# Digital_Input.net
KiCad netlist of a schematic drawn in Altium Designer
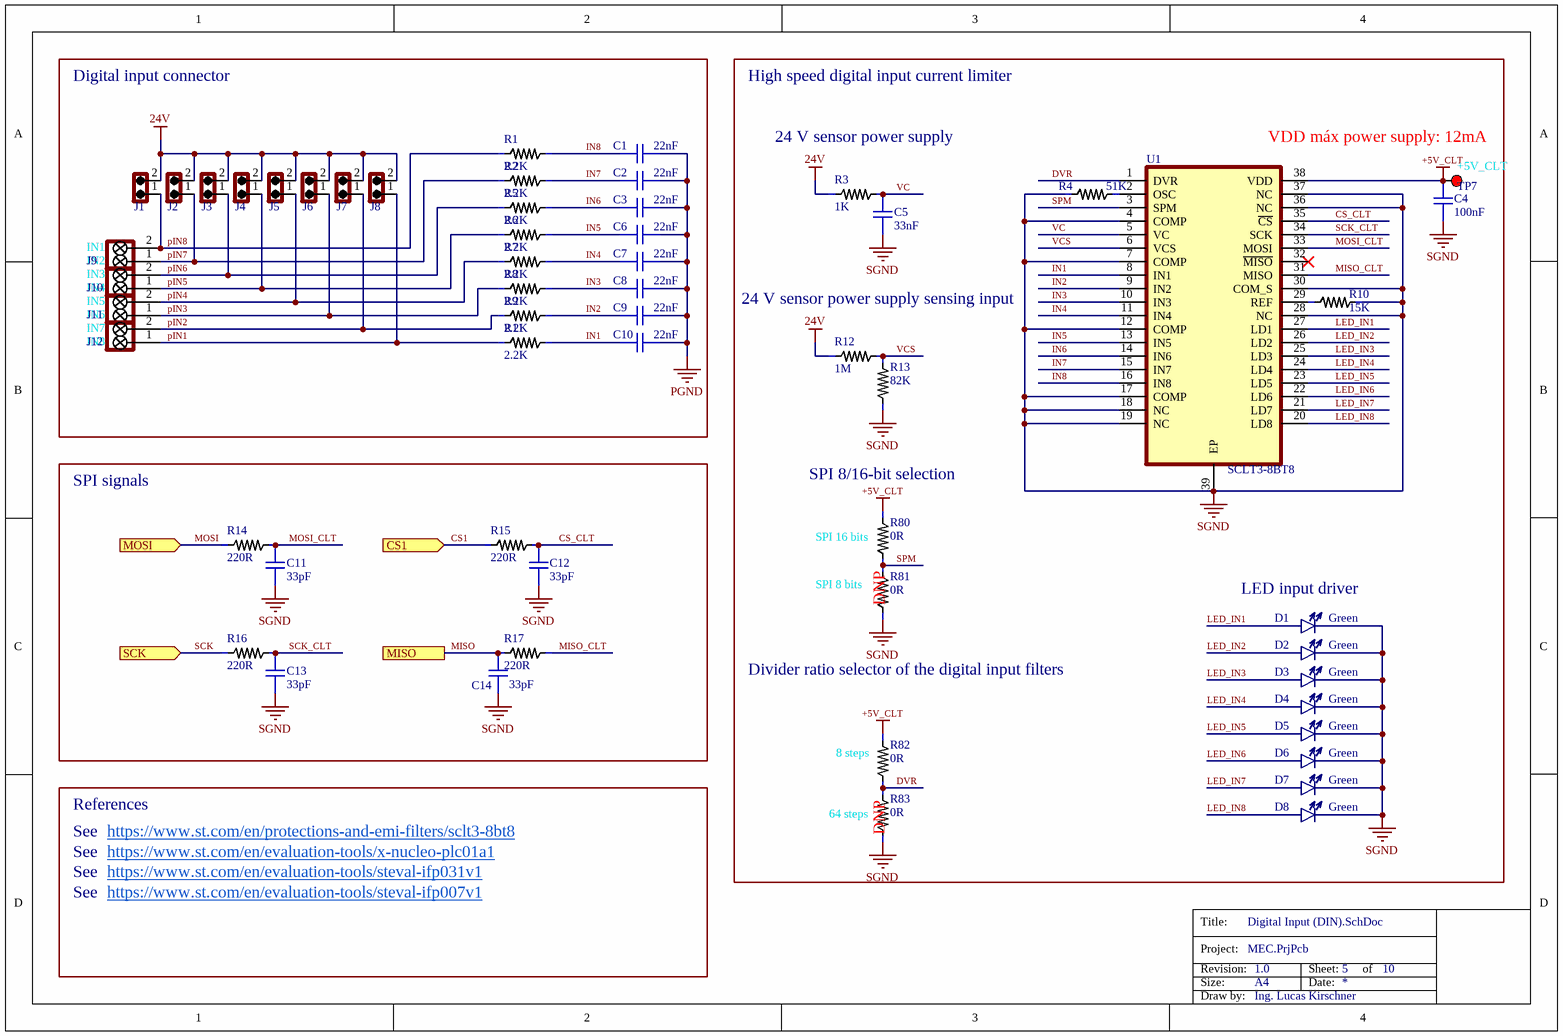
[diagram p0: Digital Input (DIN).SchDoc]

(export (version "E")
  (design (tool "Eeschema 10.0.6"))
  (components
    (comp (ref "C1")
      (value "22nF")
      (footprint "CAPC2012N")
      (description "Multilayer Ceramic Capacitors MLCC - SMD/SMT 100 V 0.022 uF X7R 0805 10%")
      (fields (field (name "PART NUMBER") "CC0805KRX7R0BB223") (field (name "MANUFACTURER") "YAGEO"))
      (libsource (lib "SchLib") (part "C-MLCC-22nF-100V-10%-0805"))
    )
    (comp (ref "C2")
      (value "22nF")
      (footprint "CAPC2012N")
      (description "Multilayer Ceramic Capacitors MLCC - SMD/SMT 100 V 0.022 uF X7R 0805 10%")
      (fields (field (name "PART NUMBER") "CC0805KRX7R0BB223") (field (name "MANUFACTURER") "YAGEO"))
      (libsource (lib "SchLib") (part "C-MLCC-22nF-100V-10%-0805"))
    )
    (comp (ref "C3")
      (value "22nF")
      (footprint "CAPC2012N")
      (description "Multilayer Ceramic Capacitors MLCC - SMD/SMT 100 V 0.022 uF X7R 0805 10%")
      (fields (field (name "PART NUMBER") "CC0805KRX7R0BB223") (field (name "MANUFACTURER") "YAGEO"))
      (libsource (lib "SchLib") (part "C-MLCC-22nF-100V-10%-0805"))
    )
    (comp (ref "C4")
      (value "100nF")
      (footprint "CAPC1005N")
      (description "Multilayer Ceramic Capacitors MLCC - SMD/SMT 50 V 0.1uF X7R 0402 10%")
      (fields (field (name "PART NUMBER") "CC0402KRX5R9BB104") (field (name "MANUFACTURER") "YAGEO"))
      (libsource (lib "SchLib") (part "C-MLCC-100nF-50V-10%-0402"))
    )
    (comp (ref "C5")
      (value "33nF")
      (footprint "CAPC2012N")
      (description "Multilayer Ceramic Capacitors MLCC - SMD/SMT 100 V 0.033 uF X7R 0805 10%")
      (fields (field (name "PART NUMBER") "CC0805KKX7R0BB333") (field (name "MANUFACTURER") "YAGEO"))
      (libsource (lib "SchLib") (part "C-MLCC-33nF-100V-10%-0805"))
    )
    (comp (ref "C6")
      (value "22nF")
      (footprint "CAPC2012N")
      (description "Multilayer Ceramic Capacitors MLCC - SMD/SMT 100 V 0.022 uF X7R 0805 10%")
      (fields (field (name "PART NUMBER") "CC0805KRX7R0BB223") (field (name "MANUFACTURER") "YAGEO"))
      (libsource (lib "SchLib") (part "C-MLCC-22nF-100V-10%-0805"))
    )
    (comp (ref "C7")
      (value "22nF")
      (footprint "CAPC2012N")
      (description "Multilayer Ceramic Capacitors MLCC - SMD/SMT 100 V 0.022 uF X7R 0805 10%")
      (fields (field (name "PART NUMBER") "CC0805KRX7R0BB223") (field (name "MANUFACTURER") "YAGEO"))
      (libsource (lib "SchLib") (part "C-MLCC-22nF-100V-10%-0805"))
    )
    (comp (ref "C8")
      (value "22nF")
      (footprint "CAPC2012N")
      (description "Multilayer Ceramic Capacitors MLCC - SMD/SMT 100 V 0.022 uF X7R 0805 10%")
      (fields (field (name "PART NUMBER") "CC0805KRX7R0BB223") (field (name "MANUFACTURER") "YAGEO"))
      (libsource (lib "SchLib") (part "C-MLCC-22nF-100V-10%-0805"))
    )
    (comp (ref "C9")
      (value "22nF")
      (footprint "CAPC2012N")
      (description "Multilayer Ceramic Capacitors MLCC - SMD/SMT 100 V 0.022 uF X7R 0805 10%")
      (fields (field (name "PART NUMBER") "CC0805KRX7R0BB223") (field (name "MANUFACTURER") "YAGEO"))
      (libsource (lib "SchLib") (part "C-MLCC-22nF-100V-10%-0805"))
    )
    (comp (ref "C10")
      (value "22nF")
      (footprint "CAPC2012N")
      (description "Multilayer Ceramic Capacitors MLCC - SMD/SMT 100 V 0.022 uF X7R 0805 10%")
      (fields (field (name "PART NUMBER") "CC0805KRX7R0BB223") (field (name "MANUFACTURER") "YAGEO"))
      (libsource (lib "SchLib") (part "C-MLCC-22nF-100V-10%-0805"))
    )
    (comp (ref "C11")
      (value "33pF")
      (footprint "CAPC1005N")
      (description "Multilayer Ceramic Capacitors MLCC - SMD/SMT 50 V 33 pF C0G 0402 1%")
      (fields (field (name "PART NUMBER") "CC0402KRNPO9BN330") (field (name "MANUFACTURER") "YAGEO"))
      (libsource (lib "SchLib") (part "C-MLCC-33pF-50V-10%-0402"))
    )
    (comp (ref "C12")
      (value "33pF")
      (footprint "CAPC1005N")
      (description "Multilayer Ceramic Capacitors MLCC - SMD/SMT 50 V 33 pF C0G 0402 1%")
      (fields (field (name "PART NUMBER") "CC0402KRNPO9BN330") (field (name "MANUFACTURER") "YAGEO"))
      (libsource (lib "SchLib") (part "C-MLCC-33pF-50V-10%-0402"))
    )
    (comp (ref "C13")
      (value "33pF")
      (footprint "CAPC1005N")
      (description "Multilayer Ceramic Capacitors MLCC - SMD/SMT 50 V 33 pF C0G 0402 1%")
      (fields (field (name "PART NUMBER") "CC0402KRNPO9BN330") (field (name "MANUFACTURER") "YAGEO"))
      (libsource (lib "SchLib") (part "C-MLCC-33pF-50V-10%-0402"))
    )
    (comp (ref "C14")
      (value "33pF")
      (footprint "CAPC1005N")
      (description "Multilayer Ceramic Capacitors MLCC - SMD/SMT 50 V 33 pF C0G 0402 1%")
      (fields (field (name "PART NUMBER") "CC0402KRNPO9BN330") (field (name "MANUFACTURER") "YAGEO"))
      (libsource (lib "SchLib") (part "C-MLCC-33pF-50V-10%-0402"))
    )
    (comp (ref "D1")
      (value "Green")
      (footprint "LEDC1608X80N_GREEN")
      (description "Standard Single Color LEDs 0603 Green")
      (fields (field (name "PART NUMBER") "LTST-C190KGKT") (field (name "MANUFACTURER") "LITEON"))
      (libsource (lib "SchLib") (part "D-LED-GREEN-2V-20mA-0603"))
    )
    (comp (ref "D2")
      (value "Green")
      (footprint "LEDC1608X80N_GREEN")
      (description "Standard Single Color LEDs 0603 Green")
      (fields (field (name "PART NUMBER") "LTST-C190KGKT") (field (name "MANUFACTURER") "LITEON"))
      (libsource (lib "SchLib") (part "D-LED-GREEN-2V-20mA-0603"))
    )
    (comp (ref "D3")
      (value "Green")
      (footprint "LEDC1608X80N_GREEN")
      (description "Standard Single Color LEDs 0603 Green")
      (fields (field (name "PART NUMBER") "LTST-C190KGKT") (field (name "MANUFACTURER") "LITEON"))
      (libsource (lib "SchLib") (part "D-LED-GREEN-2V-20mA-0603"))
    )
    (comp (ref "D4")
      (value "Green")
      (footprint "LEDC1608X80N_GREEN")
      (description "Standard Single Color LEDs 0603 Green")
      (fields (field (name "PART NUMBER") "LTST-C190KGKT") (field (name "MANUFACTURER") "LITEON"))
      (libsource (lib "SchLib") (part "D-LED-GREEN-2V-20mA-0603"))
    )
    (comp (ref "D5")
      (value "Green")
      (footprint "LEDC1608X80N_GREEN")
      (description "Standard Single Color LEDs 0603 Green")
      (fields (field (name "PART NUMBER") "LTST-C190KGKT") (field (name "MANUFACTURER") "LITEON"))
      (libsource (lib "SchLib") (part "D-LED-GREEN-2V-20mA-0603"))
    )
    (comp (ref "D6")
      (value "Green")
      (footprint "LEDC1608X80N_GREEN")
      (description "Standard Single Color LEDs 0603 Green")
      (fields (field (name "PART NUMBER") "LTST-C190KGKT") (field (name "MANUFACTURER") "LITEON"))
      (libsource (lib "SchLib") (part "D-LED-GREEN-2V-20mA-0603"))
    )
    (comp (ref "D7")
      (value "Green")
      (footprint "LEDC1608X80N_GREEN")
      (description "Standard Single Color LEDs 0603 Green")
      (fields (field (name "PART NUMBER") "LTST-C190KGKT") (field (name "MANUFACTURER") "LITEON"))
      (libsource (lib "SchLib") (part "D-LED-GREEN-2V-20mA-0603"))
    )
    (comp (ref "D8")
      (value "Green")
      (footprint "LEDC1608X80N_GREEN")
      (description "Standard Single Color LEDs 0603 Green")
      (fields (field (name "PART NUMBER") "LTST-C190KGKT") (field (name "MANUFACTURER") "LITEON"))
      (libsource (lib "SchLib") (part "D-LED-GREEN-2V-20mA-0603"))
    )
    (comp (ref "J1")
      (value "Male straight header")
      (footprint "CONH_ML254P-2N")
      (description "Male straight header, 1 row, 2 positions, 2.54mm pitch, through-hole")
      (fields (field (name "PART NUMBER") "10129378-902001BLF") (field (name "MANUFACTURER") "Amphenol FCI"))
      (libsource (lib "SchLib") (part "J-02-2P54-HDR-M-VERT-TH"))
    )
    (comp (ref "J2")
      (value "Male straight header")
      (footprint "CONH_ML254P-2N")
      (description "Male straight header, 1 row, 2 positions, 2.54mm pitch, through-hole")
      (fields (field (name "PART NUMBER") "10129378-902001BLF") (field (name "MANUFACTURER") "Amphenol FCI"))
      (libsource (lib "SchLib") (part "J-02-2P54-HDR-M-VERT-TH"))
    )
    (comp (ref "J3")
      (value "Male straight header")
      (footprint "CONH_ML254P-2N")
      (description "Male straight header, 1 row, 2 positions, 2.54mm pitch, through-hole")
      (fields (field (name "PART NUMBER") "10129378-902001BLF") (field (name "MANUFACTURER") "Amphenol FCI"))
      (libsource (lib "SchLib") (part "J-02-2P54-HDR-M-VERT-TH"))
    )
    (comp (ref "J4")
      (value "Male straight header")
      (footprint "CONH_ML254P-2N")
      (description "Male straight header, 1 row, 2 positions, 2.54mm pitch, through-hole")
      (fields (field (name "PART NUMBER") "10129378-902001BLF") (field (name "MANUFACTURER") "Amphenol FCI"))
      (libsource (lib "SchLib") (part "J-02-2P54-HDR-M-VERT-TH"))
    )
    (comp (ref "J5")
      (value "Male straight header")
      (footprint "CONH_ML254P-2N")
      (description "Male straight header, 1 row, 2 positions, 2.54mm pitch, through-hole")
      (fields (field (name "PART NUMBER") "10129378-902001BLF") (field (name "MANUFACTURER") "Amphenol FCI"))
      (libsource (lib "SchLib") (part "J-02-2P54-HDR-M-VERT-TH"))
    )
    (comp (ref "J6")
      (value "Male straight header")
      (footprint "CONH_ML254P-2N")
      (description "Male straight header, 1 row, 2 positions, 2.54mm pitch, through-hole")
      (fields (field (name "PART NUMBER") "10129378-902001BLF") (field (name "MANUFACTURER") "Amphenol FCI"))
      (libsource (lib "SchLib") (part "J-02-2P54-HDR-M-VERT-TH"))
    )
    (comp (ref "J7")
      (value "Male straight header")
      (footprint "CONH_ML254P-2N")
      (description "Male straight header, 1 row, 2 positions, 2.54mm pitch, through-hole")
      (fields (field (name "PART NUMBER") "10129378-902001BLF") (field (name "MANUFACTURER") "Amphenol FCI"))
      (libsource (lib "SchLib") (part "J-02-2P54-HDR-M-VERT-TH"))
    )
    (comp (ref "J8")
      (value "Male straight header")
      (footprint "CONH_ML254P-2N")
      (description "Male straight header, 1 row, 2 positions, 2.54mm pitch, through-hole")
      (fields (field (name "PART NUMBER") "10129378-902001BLF") (field (name "MANUFACTURER") "Amphenol FCI"))
      (libsource (lib "SchLib") (part "J-02-2P54-HDR-M-VERT-TH"))
    )
    (comp (ref "J9")
      (value "Terminal Blocks")
      (footprint "CONB_FIX508P-2N")
      (description "Pluggable Terminal Blocks 2 Pos 5.08mm pitch Through Hole Header")
      (fields (field (name "MOUSER PART #") "737-EBA-02-D-BU-01") (field (name "MANUFACTURER") "Adam Tech"))
      (libsource (lib "SchLib") (part "J-02-5P08-TERM-F-VERT-TH"))
    )
    (comp (ref "J10")
      (value "Terminal Blocks")
      (footprint "CONB_FIX508P-2N")
      (description "Pluggable Terminal Blocks 2 Pos 5.08mm pitch Through Hole Header")
      (fields (field (name "MOUSER PART #") "737-EBA-02-D-BU-01") (field (name "MANUFACTURER") "Adam Tech"))
      (libsource (lib "SchLib") (part "J-02-5P08-TERM-F-VERT-TH"))
    )
    (comp (ref "J11")
      (value "Terminal Blocks")
      (footprint "CONB_FIX508P-2N")
      (description "Pluggable Terminal Blocks 2 Pos 5.08mm pitch Through Hole Header")
      (fields (field (name "MOUSER PART #") "737-EBA-02-D-BU-01") (field (name "MANUFACTURER") "Adam Tech"))
      (libsource (lib "SchLib") (part "J-02-5P08-TERM-F-VERT-TH"))
    )
    (comp (ref "J12")
      (value "Terminal Blocks")
      (footprint "CONB_FIX508P-2N")
      (description "Pluggable Terminal Blocks 2 Pos 5.08mm pitch Through Hole Header")
      (fields (field (name "MOUSER PART #") "737-EBA-02-D-BU-01") (field (name "MANUFACTURER") "Adam Tech"))
      (libsource (lib "SchLib") (part "J-02-5P08-TERM-F-VERT-TH"))
    )
    (comp (ref "R1")
      (value "2.2K")
      (footprint "RESC2012N")
      (description "Thick Film Resistors - SMD General Purpose Chip Resistor 0805, 2.2kOhms, 1%, 1/8W")
      (fields (field (name "PART NUMBER") "RC0805FR-072K2L") (field (name "MANUFACTURER") "YAGEO"))
      (libsource (lib "SchLib") (part "R-THICK-2K2-125mW-1%-0805"))
    )
    (comp (ref "R2")
      (value "2.2K")
      (footprint "RESC2012N")
      (description "Thick Film Resistors - SMD General Purpose Chip Resistor 0805, 2.2kOhms, 1%, 1/8W")
      (fields (field (name "PART NUMBER") "RC0805FR-072K2L") (field (name "MANUFACTURER") "YAGEO"))
      (libsource (lib "SchLib") (part "R-THICK-2K2-125mW-1%-0805"))
    )
    (comp (ref "R3")
      (value "1K")
      (footprint "RESC2012N")
      (description "Thick Film Resistors - SMD General Purpose Chip Resistor 0805, 1kOhms, 1%, 1/8W")
      (fields (field (name "PART NUMBER") "RC0805FR-071KL") (field (name "MANUFACTURER") "YAGEO"))
      (libsource (lib "SchLib") (part "R-THICK-1K-125mW-1%-0805"))
    )
    (comp (ref "R4")
      (value "51K")
      (footprint "RESC1005N")
      (description "Thick Film Resistors - SMD General Purpose Chip Resistor 0402, 51kOhms, 1%, 1/16W")
      (fields (field (name "PART NUMBER") "RC0402FR-0751KL") (field (name "MANUFACTURER") "YAGEO"))
      (libsource (lib "SchLib") (part "R-THICK-51K-62.5mW-1%-0402"))
    )
    (comp (ref "R5")
      (value "2.2K")
      (footprint "RESC2012N")
      (description "Thick Film Resistors - SMD General Purpose Chip Resistor 0805, 2.2kOhms, 1%, 1/8W")
      (fields (field (name "PART NUMBER") "RC0805FR-072K2L") (field (name "MANUFACTURER") "YAGEO"))
      (libsource (lib "SchLib") (part "R-THICK-2K2-125mW-1%-0805"))
    )
    (comp (ref "R6")
      (value "2.2K")
      (footprint "RESC2012N")
      (description "Thick Film Resistors - SMD General Purpose Chip Resistor 0805, 2.2kOhms, 1%, 1/8W")
      (fields (field (name "PART NUMBER") "RC0805FR-072K2L") (field (name "MANUFACTURER") "YAGEO"))
      (libsource (lib "SchLib") (part "R-THICK-2K2-125mW-1%-0805"))
    )
    (comp (ref "R7")
      (value "2.2K")
      (footprint "RESC2012N")
      (description "Thick Film Resistors - SMD General Purpose Chip Resistor 0805, 2.2kOhms, 1%, 1/8W")
      (fields (field (name "PART NUMBER") "RC0805FR-072K2L") (field (name "MANUFACTURER") "YAGEO"))
      (libsource (lib "SchLib") (part "R-THICK-2K2-125mW-1%-0805"))
    )
    (comp (ref "R8")
      (value "2.2K")
      (footprint "RESC2012N")
      (description "Thick Film Resistors - SMD General Purpose Chip Resistor 0805, 2.2kOhms, 1%, 1/8W")
      (fields (field (name "PART NUMBER") "RC0805FR-072K2L") (field (name "MANUFACTURER") "YAGEO"))
      (libsource (lib "SchLib") (part "R-THICK-2K2-125mW-1%-0805"))
    )
    (comp (ref "R9")
      (value "2.2K")
      (footprint "RESC2012N")
      (description "Thick Film Resistors - SMD General Purpose Chip Resistor 0805, 2.2kOhms, 1%, 1/8W")
      (fields (field (name "PART NUMBER") "RC0805FR-072K2L") (field (name "MANUFACTURER") "YAGEO"))
      (libsource (lib "SchLib") (part "R-THICK-2K2-125mW-1%-0805"))
    )
    (comp (ref "R10")
      (value "15K")
      (footprint "RESC1005N")
      (description "Thick Film Resistors - SMD General Purpose Chip Resistor 0402, 15kOhms, 1%, 1/16W")
      (fields (field (name "PART NUMBER") "RC0402FR-0715KL") (field (name "MANUFACTURER") "YAGEO"))
      (libsource (lib "SchLib") (part "R-THICK-15K-62.5mW-1%-0402"))
    )
    (comp (ref "R11")
      (value "2.2K")
      (footprint "RESC2012N")
      (description "Thick Film Resistors - SMD General Purpose Chip Resistor 0805, 2.2kOhms, 1%, 1/8W")
      (fields (field (name "PART NUMBER") "RC0805FR-072K2L") (field (name "MANUFACTURER") "YAGEO"))
      (libsource (lib "SchLib") (part "R-THICK-2K2-125mW-1%-0805"))
    )
    (comp (ref "R12")
      (value "1M")
      (footprint "RESC2012N")
      (description "Thick Film Resistors - SMD General Purpose Chip Resistor 0805, 1MOhms, 1%, 1/8W")
      (fields (field (name "PART NUMBER") "RC0805FR-071ML") (field (name "MANUFACTURER") "YAGEO"))
      (libsource (lib "SchLib") (part "R-THICK-1M-125mW-1%-0805"))
    )
    (comp (ref "R13")
      (value "82K")
      (footprint "RESC2012N")
      (description "Thick Film Resistors - SMD General Purpose Chip Resistor 0805, 82 kOhms, 1%, 1/8W")
      (fields (field (name "PART NUMBER") "RC0805FR-0782KL") (field (name "MANUFACTURER") "YAGEO"))
      (libsource (lib "SchLib") (part "R-THICK-82K-125mW-1%-0805"))
    )
    (comp (ref "R14")
      (value "220R")
      (footprint "RESC1005N")
      (description "Thick Film Resistors - SMD General Purpose Chip Resistor 0402, 220Ohms, 1%, 1/16W")
      (fields (field (name "PART NUMBER") "RC0402FR-07220RL") (field (name "MANUFACTURER") "YAGEO"))
      (libsource (lib "SchLib") (part "R-THICK-220R-62.5mW-1%-0402"))
    )
    (comp (ref "R15")
      (value "220R")
      (footprint "RESC1005N")
      (description "Thick Film Resistors - SMD General Purpose Chip Resistor 0402, 220Ohms, 1%, 1/16W")
      (fields (field (name "PART NUMBER") "RC0402FR-07220RL") (field (name "MANUFACTURER") "YAGEO"))
      (libsource (lib "SchLib") (part "R-THICK-220R-62.5mW-1%-0402"))
    )
    (comp (ref "R16")
      (value "220R")
      (footprint "RESC1005N")
      (description "Thick Film Resistors - SMD General Purpose Chip Resistor 0402, 220Ohms, 1%, 1/16W")
      (fields (field (name "PART NUMBER") "RC0402FR-07220RL") (field (name "MANUFACTURER") "YAGEO"))
      (libsource (lib "SchLib") (part "R-THICK-220R-62.5mW-1%-0402"))
    )
    (comp (ref "R17")
      (value "220R")
      (footprint "RESC1005N")
      (description "Thick Film Resistors - SMD General Purpose Chip Resistor 0402, 220Ohms, 1%, 1/16W")
      (fields (field (name "PART NUMBER") "RC0402FR-07220RL") (field (name "MANUFACTURER") "YAGEO"))
      (libsource (lib "SchLib") (part "R-THICK-220R-62.5mW-1%-0402"))
    )
    (comp (ref "R80")
      (value "0R")
      (footprint "RESC1005N")
      (description "Thick Film Resistors - SMD General Purpose Chip Resistor 0402, 0Ohms, 1%, 1/16W")
      (fields (field (name "PART NUMBER") "RC0402FR-070RL") (field (name "MANUFACTURER") "YAGEO"))
      (libsource (lib "SchLib") (part "R-THICK-0R-62.5mW-1%-0402"))
    )
    (comp (ref "R81")
      (value "0R")
      (footprint "RESC1005N")
      (description "Thick Film Resistors - SMD General Purpose Chip Resistor 0402, 0Ohms, 1%, 1/16W")
      (fields (field (name "PART NUMBER") "RC0402FR-070RL") (field (name "MANUFACTURER") "YAGEO"))
      (libsource (lib "SchLib") (part "R-THICK-0R-62.5mW-1%-0402"))
    )
    (comp (ref "R82")
      (value "0R")
      (footprint "RESC1005N")
      (description "Thick Film Resistors - SMD General Purpose Chip Resistor 0402, 0Ohms, 1%, 1/16W")
      (fields (field (name "PART NUMBER") "RC0402FR-070RL") (field (name "MANUFACTURER") "YAGEO"))
      (libsource (lib "SchLib") (part "R-THICK-0R-62.5mW-1%-0402"))
    )
    (comp (ref "R83")
      (value "0R")
      (footprint "RESC1005N")
      (description "Thick Film Resistors - SMD General Purpose Chip Resistor 0402, 0Ohms, 1%, 1/16W")
      (fields (field (name "PART NUMBER") "RC0402FR-070RL") (field (name "MANUFACTURER") "YAGEO"))
      (libsource (lib "SchLib") (part "R-THICK-0R-62.5mW-1%-0402"))
    )
    (comp (ref "TP7")
      (value "Test point")
      (footprint "TP-1MM")
      (description "Test point, 1mm, exposed pad")
      (fields (field (name "JLCPCB PART #") "C5199810"))
      (libsource (lib "SchLib") (part "TP-1MM-SMD"))
    )
    (comp (ref "U1")
      (value "I/O Controller Interface")
      (footprint "SOP50P640X110-39N")
      (description "I/O Controller Interface IC 8-Line Protected Digital Serial")
      (fields
        (field (name "MANUFACTURER") "STMicroelectronics")
        (field (name "MOUSER PART #") "511-SCLT3-8BT8")
        (field (name "PART NUMBER") "SCLT3-8BT8")
      )
      (libsource (lib "SchLib") (part "U-SCLT3-8BT8"))
    )
  )
  (nets
    (net (code "1") (name "+5V_CLT") (class "Default")
      (node (ref "C4") (pin "1") (pinfunction "1_1") (pintype "passive"))
      (node (ref "R80") (pin "2") (pinfunction "2_2") (pintype "passive"))
      (node (ref "R82") (pin "2") (pinfunction "2_2") (pintype "passive"))
      (node (ref "TP7") (pin "1") (pinfunction "1_1") (pintype "passive"))
      (node (ref "U1") (pin "38") (pinfunction "VDD_38") (pintype "passive"))
    )
    (net (code "2") (name "/CS1") (class "Default")
      (node (ref "R15") (pin "1") (pinfunction "1_1") (pintype "passive"))
    )
    (net (code "3") (name "/CS_CLT") (class "Default")
      (node (ref "C12") (pin "1") (pinfunction "1_1") (pintype "passive"))
      (node (ref "R15") (pin "2") (pinfunction "2_2") (pintype "passive"))
      (node (ref "U1") (pin "35") (pinfunction "~{CS}_35") (pintype "passive"))
    )
    (net (code "4") (name "/DVR") (class "Default")
      (node (ref "R82") (pin "1") (pinfunction "1_1") (pintype "passive"))
      (node (ref "R83") (pin "2") (pinfunction "2_2") (pintype "passive"))
      (node (ref "U1") (pin "1") (pinfunction "DVR_1") (pintype "passive"))
    )
    (net (code "5") (name "/IN1") (class "Default")
      (node (ref "C10") (pin "1") (pinfunction "1_1") (pintype "passive"))
      (node (ref "R11") (pin "2") (pinfunction "2_2") (pintype "passive"))
      (node (ref "U1") (pin "8") (pinfunction "IN1_8") (pintype "passive"))
    )
    (net (code "6") (name "/IN2") (class "Default")
      (node (ref "C9") (pin "1") (pinfunction "1_1") (pintype "passive"))
      (node (ref "R9") (pin "2") (pinfunction "2_2") (pintype "passive"))
      (node (ref "U1") (pin "9") (pinfunction "IN2_9") (pintype "passive"))
    )
    (net (code "7") (name "/IN3") (class "Default")
      (node (ref "C8") (pin "1") (pinfunction "1_1") (pintype "passive"))
      (node (ref "R8") (pin "2") (pinfunction "2_2") (pintype "passive"))
      (node (ref "U1") (pin "10") (pinfunction "IN3_10") (pintype "passive"))
    )
    (net (code "8") (name "/IN4") (class "Default")
      (node (ref "C7") (pin "1") (pinfunction "1_1") (pintype "passive"))
      (node (ref "R7") (pin "2") (pinfunction "2_2") (pintype "passive"))
      (node (ref "U1") (pin "11") (pinfunction "IN4_11") (pintype "passive"))
    )
    (net (code "9") (name "/IN5") (class "Default")
      (node (ref "C6") (pin "1") (pinfunction "1_1") (pintype "passive"))
      (node (ref "R6") (pin "2") (pinfunction "2_2") (pintype "passive"))
      (node (ref "U1") (pin "13") (pinfunction "IN5_13") (pintype "passive"))
    )
    (net (code "10") (name "/IN6") (class "Default")
      (node (ref "C3") (pin "1") (pinfunction "1_1") (pintype "passive"))
      (node (ref "R5") (pin "2") (pinfunction "2_2") (pintype "passive"))
      (node (ref "U1") (pin "14") (pinfunction "IN6_14") (pintype "passive"))
    )
    (net (code "11") (name "/IN7") (class "Default")
      (node (ref "C2") (pin "1") (pinfunction "1_1") (pintype "passive"))
      (node (ref "R2") (pin "2") (pinfunction "2_2") (pintype "passive"))
      (node (ref "U1") (pin "15") (pinfunction "IN7_15") (pintype "passive"))
    )
    (net (code "12") (name "/IN8") (class "Default")
      (node (ref "C1") (pin "1") (pinfunction "1_1") (pintype "passive"))
      (node (ref "R1") (pin "2") (pinfunction "2_2") (pintype "passive"))
      (node (ref "U1") (pin "16") (pinfunction "IN8_16") (pintype "passive"))
    )
    (net (code "13") (name "/LED_IN1") (class "Default")
      (node (ref "D1") (pin "A") (pinfunction "A_A") (pintype "passive"))
      (node (ref "U1") (pin "27") (pinfunction "LD1_27") (pintype "passive"))
    )
    (net (code "14") (name "/LED_IN2") (class "Default")
      (node (ref "D2") (pin "A") (pinfunction "A_A") (pintype "passive"))
      (node (ref "U1") (pin "26") (pinfunction "LD2_26") (pintype "passive"))
    )
    (net (code "15") (name "/LED_IN3") (class "Default")
      (node (ref "D3") (pin "A") (pinfunction "A_A") (pintype "passive"))
      (node (ref "U1") (pin "25") (pinfunction "LD3_25") (pintype "passive"))
    )
    (net (code "16") (name "/LED_IN4") (class "Default")
      (node (ref "D4") (pin "A") (pinfunction "A_A") (pintype "passive"))
      (node (ref "U1") (pin "24") (pinfunction "LD4_24") (pintype "passive"))
    )
    (net (code "17") (name "/LED_IN5") (class "Default")
      (node (ref "D5") (pin "A") (pinfunction "A_A") (pintype "passive"))
      (node (ref "U1") (pin "23") (pinfunction "LD5_23") (pintype "passive"))
    )
    (net (code "18") (name "/LED_IN6") (class "Default")
      (node (ref "D6") (pin "A") (pinfunction "A_A") (pintype "passive"))
      (node (ref "U1") (pin "22") (pinfunction "LD6_22") (pintype "passive"))
    )
    (net (code "19") (name "/LED_IN7") (class "Default")
      (node (ref "D7") (pin "A") (pinfunction "A_A") (pintype "passive"))
      (node (ref "U1") (pin "21") (pinfunction "LD7_21") (pintype "passive"))
    )
    (net (code "20") (name "/LED_IN8") (class "Default")
      (node (ref "D8") (pin "A") (pinfunction "A_A") (pintype "passive"))
      (node (ref "U1") (pin "20") (pinfunction "LD8_20") (pintype "passive"))
    )
    (net (code "21") (name "/MISO") (class "Default")
      (node (ref "C14") (pin "1") (pinfunction "1_1") (pintype "passive"))
      (node (ref "R17") (pin "1") (pinfunction "1_1") (pintype "passive"))
    )
    (net (code "22") (name "/MISO_CLT") (class "Default")
      (node (ref "R17") (pin "2") (pinfunction "2_2") (pintype "passive"))
      (node (ref "U1") (pin "31") (pinfunction "MISO_31") (pintype "passive"))
    )
    (net (code "23") (name "/MOSI") (class "Default")
      (node (ref "R14") (pin "1") (pinfunction "1_1") (pintype "passive"))
    )
    (net (code "24") (name "/MOSI_CLT") (class "Default")
      (node (ref "C11") (pin "1") (pinfunction "1_1") (pintype "passive"))
      (node (ref "R14") (pin "2") (pinfunction "2_2") (pintype "passive"))
      (node (ref "U1") (pin "33") (pinfunction "MOSI_33") (pintype "passive"))
    )
    (net (code "25") (name "/SCK") (class "Default")
      (node (ref "R16") (pin "1") (pinfunction "1_1") (pintype "passive"))
    )
    (net (code "26") (name "/SCK_CLT") (class "Default")
      (node (ref "C13") (pin "1") (pinfunction "1_1") (pintype "passive"))
      (node (ref "R16") (pin "2") (pinfunction "2_2") (pintype "passive"))
      (node (ref "U1") (pin "34") (pinfunction "SCK_34") (pintype "passive"))
    )
    (net (code "27") (name "/SPM") (class "Default")
      (node (ref "R80") (pin "1") (pinfunction "1_1") (pintype "passive"))
      (node (ref "R81") (pin "2") (pinfunction "2_2") (pintype "passive"))
      (node (ref "U1") (pin "3") (pinfunction "SPM_3") (pintype "passive"))
    )
    (net (code "28") (name "/VC") (class "Default")
      (node (ref "C5") (pin "1") (pinfunction "1_1") (pintype "passive"))
      (node (ref "R3") (pin "2") (pinfunction "2_2") (pintype "passive"))
      (node (ref "U1") (pin "5") (pinfunction "VC_5") (pintype "passive"))
    )
    (net (code "29") (name "/VCS") (class "Default")
      (node (ref "R12") (pin "2") (pinfunction "2_2") (pintype "passive"))
      (node (ref "R13") (pin "2") (pinfunction "2_2") (pintype "passive"))
      (node (ref "U1") (pin "6") (pinfunction "VCS_6") (pintype "passive"))
    )
    (net (code "30") (name "/pIN1") (class "Default")
      (node (ref "J12") (pin "1") (pinfunction "1_1") (pintype "passive"))
      (node (ref "J8") (pin "1") (pinfunction "1_1") (pintype "passive"))
      (node (ref "R11") (pin "1") (pinfunction "1_1") (pintype "passive"))
    )
    (net (code "31") (name "/pIN2") (class "Default")
      (node (ref "J12") (pin "2") (pinfunction "2_2") (pintype "passive"))
      (node (ref "J7") (pin "1") (pinfunction "1_1") (pintype "passive"))
      (node (ref "R9") (pin "1") (pinfunction "1_1") (pintype "passive"))
    )
    (net (code "32") (name "/pIN3") (class "Default")
      (node (ref "J11") (pin "1") (pinfunction "1_1") (pintype "passive"))
      (node (ref "J6") (pin "1") (pinfunction "1_1") (pintype "passive"))
      (node (ref "R8") (pin "1") (pinfunction "1_1") (pintype "passive"))
    )
    (net (code "33") (name "/pIN4") (class "Default")
      (node (ref "J11") (pin "2") (pinfunction "2_2") (pintype "passive"))
      (node (ref "J5") (pin "1") (pinfunction "1_1") (pintype "passive"))
      (node (ref "R7") (pin "1") (pinfunction "1_1") (pintype "passive"))
    )
    (net (code "34") (name "/pIN5") (class "Default")
      (node (ref "J10") (pin "1") (pinfunction "1_1") (pintype "passive"))
      (node (ref "J4") (pin "1") (pinfunction "1_1") (pintype "passive"))
      (node (ref "R6") (pin "1") (pinfunction "1_1") (pintype "passive"))
    )
    (net (code "35") (name "/pIN6") (class "Default")
      (node (ref "J10") (pin "2") (pinfunction "2_2") (pintype "passive"))
      (node (ref "J3") (pin "1") (pinfunction "1_1") (pintype "passive"))
      (node (ref "R5") (pin "1") (pinfunction "1_1") (pintype "passive"))
    )
    (net (code "36") (name "/pIN7") (class "Default")
      (node (ref "J2") (pin "1") (pinfunction "1_1") (pintype "passive"))
      (node (ref "J9") (pin "1") (pinfunction "1_1") (pintype "passive"))
      (node (ref "R2") (pin "1") (pinfunction "1_1") (pintype "passive"))
    )
    (net (code "37") (name "/pIN8") (class "Default")
      (node (ref "J1") (pin "1") (pinfunction "1_1") (pintype "passive"))
      (node (ref "J9") (pin "2") (pinfunction "2_2") (pintype "passive"))
      (node (ref "R1") (pin "1") (pinfunction "1_1") (pintype "passive"))
    )
    (net (code "38") (name "24V") (class "Default")
      (node (ref "J1") (pin "2") (pinfunction "2_2") (pintype "passive"))
      (node (ref "J2") (pin "2") (pinfunction "2_2") (pintype "passive"))
      (node (ref "J3") (pin "2") (pinfunction "2_2") (pintype "passive"))
      (node (ref "J4") (pin "2") (pinfunction "2_2") (pintype "passive"))
      (node (ref "J5") (pin "2") (pinfunction "2_2") (pintype "passive"))
      (node (ref "J6") (pin "2") (pinfunction "2_2") (pintype "passive"))
      (node (ref "J7") (pin "2") (pinfunction "2_2") (pintype "passive"))
      (node (ref "J8") (pin "2") (pinfunction "2_2") (pintype "passive"))
      (node (ref "R12") (pin "1") (pinfunction "1_1") (pintype "passive"))
      (node (ref "R3") (pin "1") (pinfunction "1_1") (pintype "passive"))
    )
    (net (code "39") (name "Net-(U1-OSC)") (class "Default")
      (node (ref "R4") (pin "2") (pinfunction "2_2") (pintype "passive"))
      (node (ref "U1") (pin "2") (pinfunction "OSC_2") (pintype "passive"))
    )
    (net (code "40") (name "Net-(U1-REF)") (class "Default")
      (node (ref "R10") (pin "1") (pinfunction "1_1") (pintype "passive"))
      (node (ref "U1") (pin "29") (pinfunction "REF_29") (pintype "passive"))
    )
    (net (code "41") (name "PGND") (class "Default")
      (node (ref "C1") (pin "2") (pinfunction "2_2") (pintype "passive"))
      (node (ref "C10") (pin "2") (pinfunction "2_2") (pintype "passive"))
      (node (ref "C2") (pin "2") (pinfunction "2_2") (pintype "passive"))
      (node (ref "C3") (pin "2") (pinfunction "2_2") (pintype "passive"))
      (node (ref "C6") (pin "2") (pinfunction "2_2") (pintype "passive"))
      (node (ref "C7") (pin "2") (pinfunction "2_2") (pintype "passive"))
      (node (ref "C8") (pin "2") (pinfunction "2_2") (pintype "passive"))
      (node (ref "C9") (pin "2") (pinfunction "2_2") (pintype "passive"))
    )
    (net (code "42") (name "SGND") (class "Default")
      (node (ref "C11") (pin "2") (pinfunction "2_2") (pintype "passive"))
      (node (ref "C12") (pin "2") (pinfunction "2_2") (pintype "passive"))
      (node (ref "C13") (pin "2") (pinfunction "2_2") (pintype "passive"))
      (node (ref "C14") (pin "2") (pinfunction "2_2") (pintype "passive"))
      (node (ref "C4") (pin "2") (pinfunction "2_2") (pintype "passive"))
      (node (ref "C5") (pin "2") (pinfunction "2_2") (pintype "passive"))
      (node (ref "D1") (pin "C") (pinfunction "C_C") (pintype "passive"))
      (node (ref "D2") (pin "C") (pinfunction "C_C") (pintype "passive"))
      (node (ref "D3") (pin "C") (pinfunction "C_C") (pintype "passive"))
      (node (ref "D4") (pin "C") (pinfunction "C_C") (pintype "passive"))
      (node (ref "D5") (pin "C") (pinfunction "C_C") (pintype "passive"))
      (node (ref "D6") (pin "C") (pinfunction "C_C") (pintype "passive"))
      (node (ref "D7") (pin "C") (pinfunction "C_C") (pintype "passive"))
      (node (ref "D8") (pin "C") (pinfunction "C_C") (pintype "passive"))
      (node (ref "R10") (pin "2") (pinfunction "2_2") (pintype "passive"))
      (node (ref "R13") (pin "1") (pinfunction "1_1") (pintype "passive"))
      (node (ref "R4") (pin "1") (pinfunction "1_1") (pintype "passive"))
      (node (ref "R81") (pin "1") (pinfunction "1_1") (pintype "passive"))
      (node (ref "R83") (pin "1") (pinfunction "1_1") (pintype "passive"))
      (node (ref "U1") (pin "12") (pinfunction "COMP_12") (pintype "passive"))
      (node (ref "U1") (pin "17") (pinfunction "COMP_17") (pintype "passive"))
      (node (ref "U1") (pin "18") (pinfunction "NC_18") (pintype "passive"))
      (node (ref "U1") (pin "19") (pinfunction "NC_19") (pintype "passive"))
      (node (ref "U1") (pin "28") (pinfunction "NC_28") (pintype "passive"))
      (node (ref "U1") (pin "30") (pinfunction "COM_S_30") (pintype "passive"))
      (node (ref "U1") (pin "36") (pinfunction "NC_36") (pintype "passive"))
      (node (ref "U1") (pin "37") (pinfunction "NC_37") (pintype "passive"))
      (node (ref "U1") (pin "39") (pinfunction "EP_39") (pintype "passive"))
      (node (ref "U1") (pin "4") (pinfunction "COMP_4") (pintype "passive"))
      (node (ref "U1") (pin "7") (pinfunction "COMP_7") (pintype "passive"))
    )
    (net (code "43") (name "unconnected-(U1-~{MISO}-Pad32)") (class "Default")
      (node (ref "U1") (pin "32") (pinfunction "~{MISO}_32") (pintype "passive+no_connect"))
    )
  )
)
